# circuito.net
KiCad netlist of a schematic drawn in EAGLE
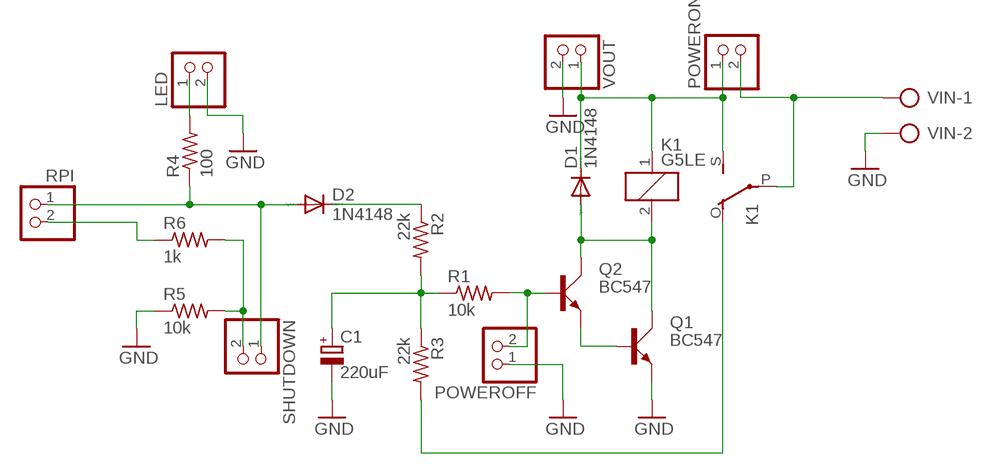
[diagram p0: schematic, sheet 1]

(export (version "E")
  (design (tool "Eeschema 10.0.6"))
  (components
    (comp (ref "C1")
      (value "220uF")
      (footprint "eagle-import:E2,5-6E")
      (libsource (lib "eagle-import") (part "CPOL-EUE2,5-6E"))
    )
    (comp (ref "D1")
      (value "1N4148")
      (footprint "eagle-import:DO35-7")
      (libsource (lib "eagle-import") (part "1N4148DO35-7"))
    )
    (comp (ref "D2")
      (value "1N4148")
      (footprint "eagle-import:DO35-7")
      (libsource (lib "eagle-import") (part "1N4148DO35-7"))
    )
    (comp (ref "K1")
      (value "G5LE")
      (footprint "eagle-import:G5LE")
      (libsource (lib "eagle-import") (part "G5LE"))
    )
    (comp (ref "LED")
      (value "PINHD-1X2")
      (footprint "eagle-import:1X02")
      (libsource (lib "eagle-import") (part "PINHD-1X2"))
    )
    (comp (ref "POWEROFF")
      (value "PINHD-1X2")
      (footprint "eagle-import:1X02")
      (libsource (lib "eagle-import") (part "PINHD-1X2"))
    )
    (comp (ref "POWERON")
      (value "PINHD-1X2")
      (footprint "eagle-import:1X02")
      (libsource (lib "eagle-import") (part "PINHD-1X2"))
    )
    (comp (ref "Q1")
      (value "BC547")
      (footprint "eagle-import:SOT54A")
      (libsource (lib "eagle-import") (part "BC547"))
    )
    (comp (ref "Q2")
      (value "BC547")
      (footprint "eagle-import:SOT54A")
      (libsource (lib "eagle-import") (part "BC547"))
    )
    (comp (ref "R1")
      (value "10k")
      (footprint "eagle-import:0207_7")
      (libsource (lib "eagle-import") (part "R-US_0207/7"))
    )
    (comp (ref "R2")
      (value "22k")
      (footprint "eagle-import:0207_7")
      (libsource (lib "eagle-import") (part "R-US_0207/7"))
    )
    (comp (ref "R3")
      (value "22k")
      (footprint "eagle-import:0207_7")
      (libsource (lib "eagle-import") (part "R-US_0207/7"))
    )
    (comp (ref "R4")
      (value "100")
      (footprint "eagle-import:0207_7")
      (libsource (lib "eagle-import") (part "R-US_0207/7"))
    )
    (comp (ref "R5")
      (value "10k")
      (footprint "eagle-import:0207_7")
      (libsource (lib "eagle-import") (part "R-US_0207/7"))
    )
    (comp (ref "R6")
      (value "1k")
      (footprint "eagle-import:0207_7")
      (libsource (lib "eagle-import") (part "R-US_0207/7"))
    )
    (comp (ref "RPI")
      (value "PINHD-1X2")
      (footprint "eagle-import:1X02")
      (libsource (lib "eagle-import") (part "PINHD-1X2"))
    )
    (comp (ref "SHUTDOWN")
      (value "PINHD-1X2")
      (footprint "eagle-import:1X02")
      (libsource (lib "eagle-import") (part "PINHD-1X2"))
    )
    (comp (ref "VIN")
      (value "AK500/2-H")
      (footprint "eagle-import:AK500_2-H")
      (libsource (lib "eagle-import") (part "AK500/2-H"))
    )
    (comp (ref "VOUT")
      (value "PINHD-1X2")
      (footprint "eagle-import:1X02")
      (libsource (lib "eagle-import") (part "PINHD-1X2"))
    )
  )
  (nets
    (net (code "1") (name "GND") (class "Default")
      (node (ref "C1") (pin "-") (pinfunction "-_-") (pintype "passive"))
      (node (ref "LED") (pin "2") (pinfunction "2_2") (pintype "passive"))
      (node (ref "POWEROFF") (pin "1") (pinfunction "1_1") (pintype "passive"))
      (node (ref "Q1") (pin "E") (pinfunction "E_E") (pintype "passive"))
      (node (ref "R5") (pin "1") (pinfunction "1_1") (pintype "passive"))
      (node (ref "VIN") (pin "2") (pinfunction "KL_2") (pintype "passive"))
      (node (ref "VOUT") (pin "2") (pinfunction "2_2") (pintype "passive"))
    )
    (net (code "2") (name "Net-(C1-Pad+)") (class "Default")
      (node (ref "C1") (pin "+") (pinfunction "+_+") (pintype "passive"))
      (node (ref "R1") (pin "1") (pinfunction "1_1") (pintype "passive"))
      (node (ref "R2") (pin "2") (pinfunction "2_2") (pintype "passive"))
      (node (ref "R3") (pin "1") (pinfunction "1_1") (pintype "passive"))
    )
    (net (code "3") (name "Net-(D1-PadA)") (class "Default")
      (node (ref "D1") (pin "A") (pinfunction "A_A") (pintype "passive"))
      (node (ref "K1") (pin "2") (pinfunction "2_2") (pintype "passive"))
      (node (ref "Q1") (pin "C") (pinfunction "C_C") (pintype "passive"))
      (node (ref "Q2") (pin "C") (pinfunction "C_C") (pintype "passive"))
    )
    (net (code "4") (name "Net-(D1-PadC)") (class "Default")
      (node (ref "D1") (pin "C") (pinfunction "C_C") (pintype "passive"))
      (node (ref "K1") (pin "1") (pinfunction "1_1") (pintype "passive"))
      (node (ref "K1") (pin "S") (pinfunction "S_S") (pintype "passive"))
      (node (ref "POWERON") (pin "1") (pinfunction "1_1") (pintype "passive"))
      (node (ref "VOUT") (pin "1") (pinfunction "1_1") (pintype "passive"))
    )
    (net (code "5") (name "Net-(D2-PadA)") (class "Default")
      (node (ref "D2") (pin "A") (pinfunction "A_A") (pintype "passive"))
      (node (ref "R4") (pin "1") (pinfunction "1_1") (pintype "passive"))
      (node (ref "RPI") (pin "1") (pinfunction "1_1") (pintype "passive"))
      (node (ref "SHUTDOWN") (pin "1") (pinfunction "1_1") (pintype "passive"))
    )
    (net (code "6") (name "Net-(D2-PadC)") (class "Default")
      (node (ref "D2") (pin "C") (pinfunction "C_C") (pintype "passive"))
      (node (ref "R2") (pin "1") (pinfunction "1_1") (pintype "passive"))
    )
    (net (code "7") (name "Net-(K1-PadO)") (class "Default")
      (node (ref "K1") (pin "O") (pinfunction "O_O") (pintype "passive"))
      (node (ref "R3") (pin "2") (pinfunction "2_2") (pintype "passive"))
    )
    (net (code "8") (name "Net-(LED-Pad1)") (class "Default")
      (node (ref "LED") (pin "1") (pinfunction "1_1") (pintype "passive"))
      (node (ref "R4") (pin "2") (pinfunction "2_2") (pintype "passive"))
    )
    (net (code "9") (name "Net-(POWEROFF-Pad2)") (class "Default")
      (node (ref "POWEROFF") (pin "2") (pinfunction "2_2") (pintype "passive"))
      (node (ref "Q2") (pin "B") (pinfunction "B_B") (pintype "passive"))
      (node (ref "R1") (pin "2") (pinfunction "2_2") (pintype "passive"))
    )
    (net (code "10") (name "Net-(Q1-PadB)") (class "Default")
      (node (ref "Q1") (pin "B") (pinfunction "B_B") (pintype "passive"))
      (node (ref "Q2") (pin "E") (pinfunction "E_E") (pintype "passive"))
    )
    (net (code "11") (name "Net-(R5-Pad2)") (class "Default")
      (node (ref "R5") (pin "2") (pinfunction "2_2") (pintype "passive"))
      (node (ref "R6") (pin "2") (pinfunction "2_2") (pintype "passive"))
      (node (ref "SHUTDOWN") (pin "2") (pinfunction "2_2") (pintype "passive"))
    )
    (net (code "12") (name "Net-(R6-Pad1)") (class "Default")
      (node (ref "R6") (pin "1") (pinfunction "1_1") (pintype "passive"))
      (node (ref "RPI") (pin "2") (pinfunction "2_2") (pintype "passive"))
    )
    (net (code "13") (name "Net-(VINA-KL)") (class "Default")
      (node (ref "K1") (pin "P") (pinfunction "P_P") (pintype "passive"))
      (node (ref "POWERON") (pin "2") (pinfunction "2_2") (pintype "passive"))
      (node (ref "VIN") (pin "1") (pinfunction "KL_1") (pintype "passive"))
    )
  )
)
